# TFT_MicroSD.net
KiCad netlist of a schematic drawn in Altium Designer
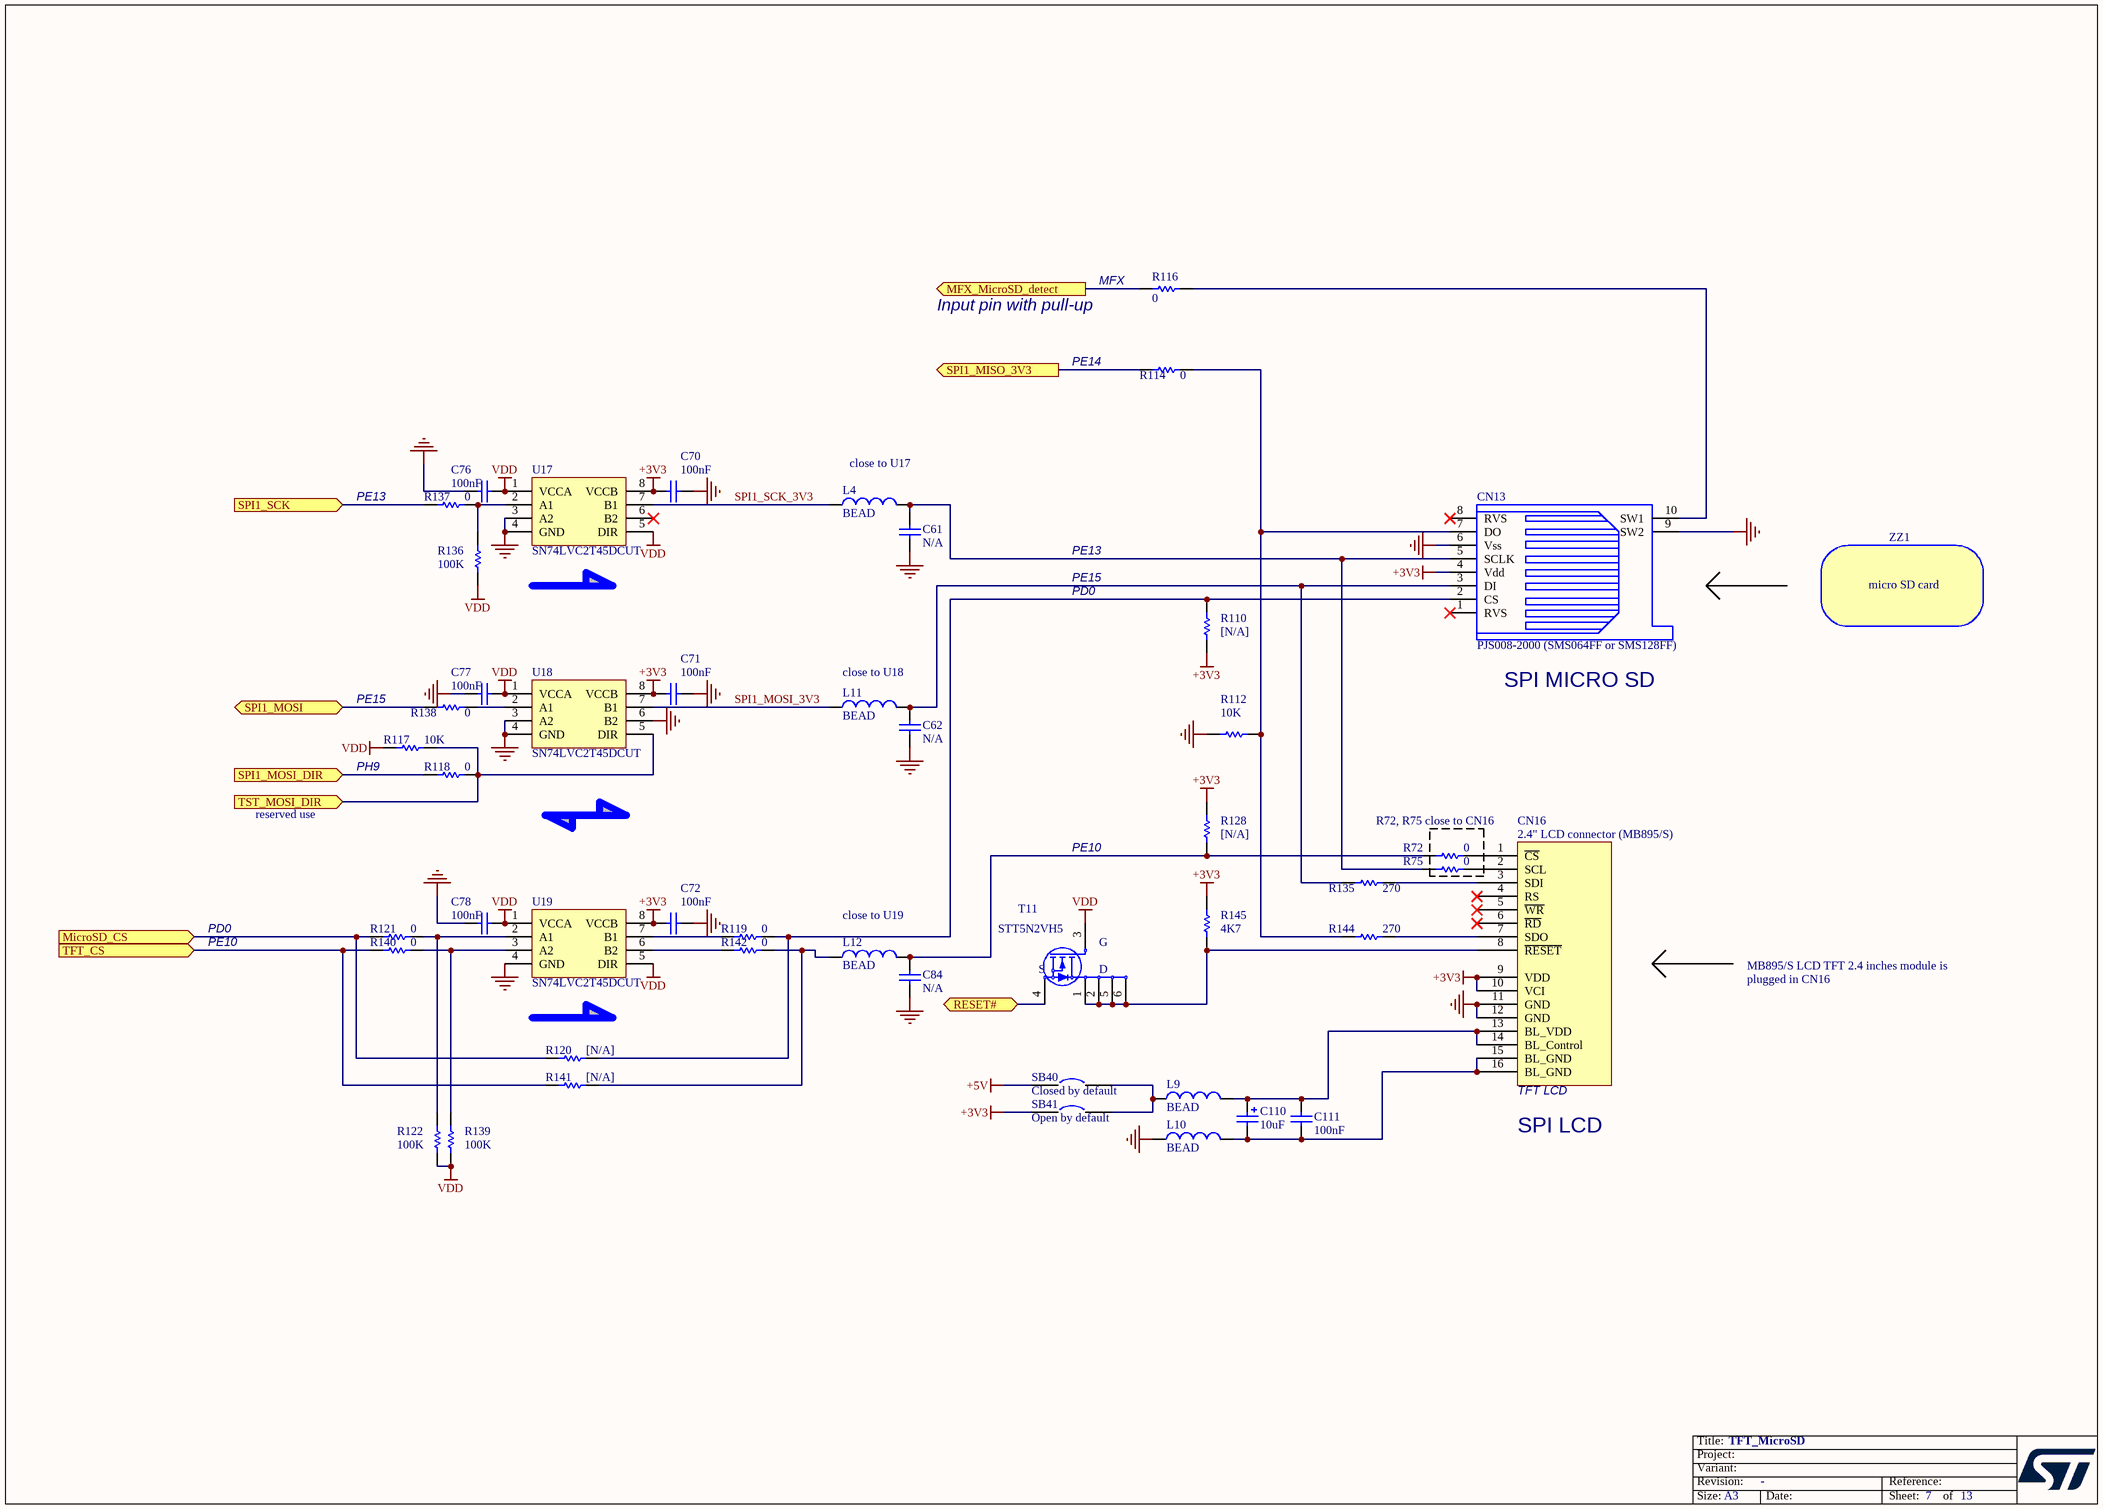
[diagram p0: TFT_MicroSD.SchDoc]

(export (version "E")
  (design (tool "Eeschema 10.0.6"))
  (components
    (comp (ref "C61")
      (value "N/A")
      (footprint "0603C")
      (description "Capacitor")
      (fields (field (name "PUBLISHER") "Altium Limited"))
      (libsource (lib "Miscellaneous Devices") (part "CAP"))
    )
    (comp (ref "C62")
      (value "N/A")
      (footprint "0603C")
      (description "Capacitor")
      (fields (field (name "PUBLISHER") "Altium Limited"))
      (libsource (lib "Miscellaneous Devices") (part "CAP"))
    )
    (comp (ref "C70")
      (value "100nF")
      (footprint "0402C")
      (description "Capacitor")
      (fields (field (name "PUBLISHER") "Altium Limited"))
      (libsource (lib "Miscellaneous Devices") (part "CAP"))
    )
    (comp (ref "C71")
      (value "100nF")
      (footprint "0402C")
      (description "Capacitor")
      (fields (field (name "PUBLISHER") "Altium Limited"))
      (libsource (lib "Miscellaneous Devices") (part "CAP"))
    )
    (comp (ref "C72")
      (value "100nF")
      (footprint "0402C")
      (description "Capacitor")
      (fields (field (name "PUBLISHER") "Altium Limited"))
      (libsource (lib "Miscellaneous Devices") (part "CAP"))
    )
    (comp (ref "C76")
      (value "100nF")
      (footprint "0402C")
      (description "Capacitor")
      (fields (field (name "PUBLISHER") "Altium Limited"))
      (libsource (lib "Miscellaneous Devices") (part "CAP"))
    )
    (comp (ref "C77")
      (value "100nF")
      (footprint "0402C")
      (description "Capacitor")
      (fields (field (name "PUBLISHER") "Altium Limited"))
      (libsource (lib "Miscellaneous Devices") (part "CAP"))
    )
    (comp (ref "C78")
      (value "100nF")
      (footprint "0402C")
      (description "Capacitor")
      (fields (field (name "PUBLISHER") "Altium Limited"))
      (libsource (lib "Miscellaneous Devices") (part "CAP"))
    )
    (comp (ref "C84")
      (value "N/A")
      (footprint "0603C")
      (description "Capacitor")
      (fields (field (name "PUBLISHER") "Altium Limited"))
      (libsource (lib "Miscellaneous Devices") (part "CAP"))
    )
    (comp (ref "C110")
      (value "10uF")
      (footprint "TAN-A")
      (description "Polarized Capacitor (Radial)")
      (fields (field (name "PUBLISHER") "Altium Limited"))
      (libsource (lib "Miscellaneous Devices") (part "Cap Pol1"))
    )
    (comp (ref "C111")
      (value "100nF")
      (footprint "0402C")
      (description "Capacitor")
      (fields (field (name "PUBLISHER") "Altium Limited"))
      (libsource (lib "Miscellaneous Devices") (part "Cap"))
    )
    (comp (ref "CN13")
      (value "PJS008-2000 (SMS064FF or SMS128FF)")
      (footprint "MSD_PJS008_")
      (libsource (lib "MB1070") (part "SMS016AFA5E"))
    )
    (comp (ref "CN16")
      (value "2.4\" LCD connector (MB895/S)")
      (footprint "MB895CS")
      (libsource (lib "MB1070") (part "ColorLCD_module"))
    )
    (comp (ref "L4")
      (value "BEAD")
      (footprint "0603L")
      (description "Bead,600R,350mA,0603")
      (fields (field (name "PUBLISHER") "Altium Limited"))
      (libsource (lib "Miscellaneous Devices") (part "Inductor"))
    )
    (comp (ref "L9")
      (value "BEAD")
      (footprint "0603L")
      (description "Bead,600R,350mA,0603")
      (fields (field (name "PUBLISHER") "Altium Limited"))
      (libsource (lib "Miscellaneous Devices") (part "Inductor"))
    )
    (comp (ref "L10")
      (value "BEAD")
      (footprint "0603L")
      (description "Bead,600R,350mA,0603")
      (fields (field (name "PUBLISHER") "Altium Limited"))
      (libsource (lib "Miscellaneous Devices") (part "Inductor"))
    )
    (comp (ref "L11")
      (value "BEAD")
      (footprint "0603L")
      (description "Bead,600R,350mA,0603")
      (fields (field (name "PUBLISHER") "Altium Limited"))
      (libsource (lib "Miscellaneous Devices") (part "Inductor"))
    )
    (comp (ref "L12")
      (value "BEAD")
      (footprint "0603L")
      (description "Bead,600R,350mA,0603")
      (fields (field (name "PUBLISHER") "Altium Limited"))
      (libsource (lib "Miscellaneous Devices") (part "Inductor"))
    )
    (comp (ref "R72")
      (value "0")
      (footprint "0603R")
      (description "Resistor")
      (fields (field (name "PUBLISHER") "Altium Limited"))
      (libsource (lib "Miscellaneous Devices") (part "Res1"))
    )
    (comp (ref "R75")
      (value "0")
      (footprint "0603R")
      (description "Resistor")
      (fields (field (name "PUBLISHER") "Altium Limited"))
      (libsource (lib "Miscellaneous Devices") (part "Res1"))
    )
    (comp (ref "R110")
      (value "[N/A]")
      (footprint "0603R")
      (description "Resistor")
      (fields (field (name "PUBLISHER") "Altium Limited"))
      (libsource (lib "Miscellaneous Devices") (part "Res1"))
    )
    (comp (ref "R112")
      (value "10K")
      (footprint "0402R")
      (description "Resistor")
      (fields (field (name "PUBLISHER") "Altium Limited"))
      (libsource (lib "Miscellaneous Devices") (part "Res1"))
    )
    (comp (ref "R114")
      (value "0")
      (footprint "0603R")
      (description "Resistor")
      (fields (field (name "PUBLISHER") "Altium Limited"))
      (libsource (lib "Miscellaneous Devices") (part "Res1"))
    )
    (comp (ref "R116")
      (value "0")
      (footprint "0603R")
      (description "Resistor")
      (fields (field (name "PUBLISHER") "Altium Limited"))
      (libsource (lib "Miscellaneous Devices") (part "Res1"))
    )
    (comp (ref "R117")
      (value "10K")
      (footprint "0402R")
      (description "Resistor")
      (fields (field (name "PUBLISHER") "Altium Limited"))
      (libsource (lib "Miscellaneous Devices") (part "Res1"))
    )
    (comp (ref "R118")
      (value "0")
      (footprint "0603R")
      (description "Resistor")
      (fields (field (name "PUBLISHER") "Altium Limited"))
      (libsource (lib "Miscellaneous Devices") (part "Res1"))
    )
    (comp (ref "R119")
      (value "0")
      (footprint "0603R")
      (description "Resistor")
      (fields (field (name "PUBLISHER") "Altium Limited"))
      (libsource (lib "Miscellaneous Devices") (part "res1"))
    )
    (comp (ref "R120")
      (value "[N/A]")
      (footprint "0603R")
      (description "Resistor")
      (fields (field (name "PUBLISHER") "Altium Limited"))
      (libsource (lib "Miscellaneous Devices") (part "Res1"))
    )
    (comp (ref "R121")
      (value "0")
      (footprint "0603R")
      (description "Resistor")
      (fields (field (name "PUBLISHER") "Altium Limited"))
      (libsource (lib "Miscellaneous Devices") (part "res1"))
    )
    (comp (ref "R122")
      (value "100K")
      (footprint "0603R")
      (description "Resistor")
      (fields (field (name "PUBLISHER") "Altium Limited"))
      (libsource (lib "Miscellaneous Devices") (part "Res1"))
    )
    (comp (ref "R128")
      (value "[N/A]")
      (footprint "0603R")
      (description "Resistor")
      (fields (field (name "PUBLISHER") "Altium Limited"))
      (libsource (lib "Miscellaneous Devices") (part "Res1"))
    )
    (comp (ref "R135")
      (value "270")
      (footprint "0603R")
      (description "Resistor")
      (fields (field (name "PUBLISHER") "Altium Limited"))
      (libsource (lib "Miscellaneous Devices") (part "Res1"))
    )
    (comp (ref "R136")
      (value "100K")
      (footprint "0603R")
      (description "Resistor")
      (fields (field (name "PUBLISHER") "Altium Limited"))
      (libsource (lib "Miscellaneous Devices") (part "Res1"))
    )
    (comp (ref "R137")
      (value "0")
      (footprint "0603R")
      (description "Resistor")
      (fields (field (name "PUBLISHER") "Altium Limited"))
      (libsource (lib "Miscellaneous Devices") (part "res1"))
    )
    (comp (ref "R138")
      (value "0")
      (footprint "0603R")
      (description "Resistor")
      (fields (field (name "PUBLISHER") "Altium Limited"))
      (libsource (lib "Miscellaneous Devices") (part "res1"))
    )
    (comp (ref "R139")
      (value "100K")
      (footprint "0603R")
      (description "Resistor")
      (fields (field (name "PUBLISHER") "Altium Limited"))
      (libsource (lib "Miscellaneous Devices") (part "Res1"))
    )
    (comp (ref "R140")
      (value "0")
      (footprint "0603R")
      (description "Resistor")
      (fields (field (name "PUBLISHER") "Altium Limited"))
      (libsource (lib "Miscellaneous Devices") (part "Res1"))
    )
    (comp (ref "R141")
      (value "[N/A]")
      (footprint "0603R")
      (description "Resistor")
      (fields (field (name "PUBLISHER") "Altium Limited"))
      (libsource (lib "Miscellaneous Devices") (part "Res1"))
    )
    (comp (ref "R142")
      (value "0")
      (footprint "0603R")
      (description "Resistor")
      (fields (field (name "PUBLISHER") "Altium Limited"))
      (libsource (lib "Miscellaneous Devices") (part "res1"))
    )
    (comp (ref "R144")
      (value "270")
      (footprint "0603R")
      (description "Resistor")
      (fields (field (name "PUBLISHER") "Altium Limited"))
      (libsource (lib "Miscellaneous Devices") (part "Res1"))
    )
    (comp (ref "R145")
      (value "4K7")
      (footprint "0402R")
      (description "Resistor")
      (fields (field (name "PUBLISHER") "Altium Limited"))
      (libsource (lib "Miscellaneous Devices") (part "Res1"))
    )
    (comp (ref "SB40")
      (value "Closed by default")
      (footprint "SB_0603")
      (description "Circuit Breaker")
      (fields (field (name "PUBLISHER") "Altium Limited"))
      (libsource (lib "Miscellaneous Devices") (part "Circuit Breaker"))
    )
    (comp (ref "SB41")
      (value "Open by default")
      (footprint "SB_0603")
      (description "Circuit Breaker")
      (fields (field (name "PUBLISHER") "Altium Limited"))
      (libsource (lib "Miscellaneous Devices") (part "Circuit Breaker"))
    )
    (comp (ref "T11")
      (value "STT5N2VH5")
      (footprint "SOT23-6L")
      (description "STripFETV Power MOSFET, N-CHANNEL 20V - 0.025 - 5A - SOT23-6L")
      (libsource (lib "MCD_TOOLS") (part "STT5N2VH5"))
    )
    (comp (ref "U17")
      (value "SN74LVC2T45DCUT")
      (footprint "USOP8_0R5_2X3R1")
      (libsource (lib "MB818") (part "SN74LVC2T45DCUT"))
    )
    (comp (ref "U18")
      (value "SN74LVC2T45DCUT")
      (footprint "USOP8_0R5_2X3R1")
      (libsource (lib "MB818") (part "SN74LVC2T45DCUT"))
    )
    (comp (ref "U19")
      (value "SN74LVC2T45DCUT")
      (footprint "USOP8_0R5_2X3R1")
      (libsource (lib "MB818") (part "SN74LVC2T45DCUT"))
    )
    (comp (ref "ZZ1")
      (value "micro SD card")
      (description "4GB or more")
      (libsource (lib "Almos") (part "BoM_Item"))
    )
  )
  (nets
    (net (code "1") (name "+3V3") (class "Default")
      (node (ref "C70") (pin "2") (pinfunction "2_2") (pintype "passive"))
      (node (ref "C71") (pin "2") (pinfunction "2_2") (pintype "passive"))
      (node (ref "C72") (pin "2") (pinfunction "2_2") (pintype "passive"))
      (node (ref "CN13") (pin "4") (pinfunction "Vdd_4") (pintype "passive"))
      (node (ref "CN16") (pin "10") (pinfunction "VCI_10") (pintype "passive"))
      (node (ref "CN16") (pin "9") (pinfunction "VDD_9") (pintype "passive"))
      (node (ref "R110") (pin "2") (pinfunction "2_2") (pintype "passive"))
      (node (ref "R128") (pin "2") (pinfunction "2_2") (pintype "passive"))
      (node (ref "R145") (pin "2") (pinfunction "2_2") (pintype "passive"))
      (node (ref "SB41") (pin "1") (pinfunction "1_1") (pintype "passive"))
      (node (ref "U17") (pin "8") (pinfunction "VCCB_8") (pintype "passive"))
      (node (ref "U18") (pin "8") (pinfunction "VCCB_8") (pintype "passive"))
      (node (ref "U19") (pin "8") (pinfunction "VCCB_8") (pintype "passive"))
    )
    (net (code "2") (name "+5V") (class "Default")
      (node (ref "SB40") (pin "1") (pinfunction "1_1") (pintype "passive"))
    )
    (net (code "3") (name "/MFX_MicroSD_detect") (class "Default")
      (node (ref "R116") (pin "1") (pinfunction "1_1") (pintype "passive"))
    )
    (net (code "4") (name "/MicroSD_CS") (class "Default")
      (node (ref "R120") (pin "1") (pinfunction "1_1") (pintype "passive"))
      (node (ref "R121") (pin "2") (pinfunction "2_2") (pintype "passive"))
    )
    (net (code "5") (name "/RESET#") (class "Default")
      (node (ref "T11") (pin "4") (pinfunction "S_4") (pintype "passive"))
    )
    (net (code "6") (name "/SPI1_MISO_3V3") (class "Default")
      (node (ref "R114") (pin "2") (pinfunction "2_2") (pintype "passive"))
    )
    (net (code "7") (name "/SPI1_MOSI") (class "Default")
      (node (ref "R138") (pin "2") (pinfunction "2_2") (pintype "passive"))
    )
    (net (code "8") (name "/SPI1_MOSI_3V3") (class "Default")
      (node (ref "L11") (pin "1") (pinfunction "1_1") (pintype "passive"))
      (node (ref "U18") (pin "7") (pinfunction "B1_7") (pintype "passive"))
    )
    (net (code "9") (name "/SPI1_MOSI_DIR") (class "Default")
      (node (ref "R118") (pin "2") (pinfunction "2_2") (pintype "passive"))
    )
    (net (code "10") (name "/SPI1_SCK") (class "Default")
      (node (ref "R137") (pin "2") (pinfunction "2_2") (pintype "passive"))
    )
    (net (code "11") (name "/SPI1_SCK_3V3") (class "Default")
      (node (ref "L4") (pin "1") (pinfunction "1_1") (pintype "passive"))
      (node (ref "U17") (pin "7") (pinfunction "B1_7") (pintype "passive"))
    )
    (net (code "12") (name "/TFT_CS") (class "Default")
      (node (ref "R140") (pin "1") (pinfunction "1_1") (pintype "passive"))
      (node (ref "R141") (pin "1") (pinfunction "1_1") (pintype "passive"))
    )
    (net (code "13") (name "/TST_MOSI_DIR") (class "Default")
      (node (ref "R117") (pin "1") (pinfunction "1_1") (pintype "passive"))
      (node (ref "R118") (pin "1") (pinfunction "1_1") (pintype "passive"))
      (node (ref "U18") (pin "5") (pinfunction "DIR_5") (pintype "passive"))
    )
    (net (code "14") (name "GND") (class "Default")
      (node (ref "C61") (pin "1") (pinfunction "1_1") (pintype "passive"))
      (node (ref "C62") (pin "1") (pinfunction "1_1") (pintype "passive"))
      (node (ref "C70") (pin "1") (pinfunction "1_1") (pintype "passive"))
      (node (ref "C71") (pin "1") (pinfunction "1_1") (pintype "passive"))
      (node (ref "C72") (pin "1") (pinfunction "1_1") (pintype "passive"))
      (node (ref "C76") (pin "1") (pinfunction "1_1") (pintype "passive"))
      (node (ref "C77") (pin "1") (pinfunction "1_1") (pintype "passive"))
      (node (ref "C78") (pin "1") (pinfunction "1_1") (pintype "passive"))
      (node (ref "C84") (pin "1") (pinfunction "1_1") (pintype "passive"))
      (node (ref "CN13") (pin "6") (pinfunction "Vss_6") (pintype "passive"))
      (node (ref "CN13") (pin "9") (pinfunction "SW2_9") (pintype "passive"))
      (node (ref "CN16") (pin "11") (pinfunction "GND_11") (pintype "passive"))
      (node (ref "CN16") (pin "12") (pinfunction "GND_12") (pintype "passive"))
      (node (ref "L10") (pin "1") (pinfunction "1_1") (pintype "passive"))
      (node (ref "R112") (pin "1") (pinfunction "1_1") (pintype "passive"))
      (node (ref "U17") (pin "3") (pinfunction "A2_3") (pintype "passive"))
      (node (ref "U17") (pin "4") (pinfunction "GND_4") (pintype "passive"))
      (node (ref "U18") (pin "3") (pinfunction "A2_3") (pintype "passive"))
      (node (ref "U18") (pin "4") (pinfunction "GND_4") (pintype "passive"))
      (node (ref "U18") (pin "6") (pinfunction "B2_6") (pintype "passive"))
      (node (ref "U19") (pin "4") (pinfunction "GND_4") (pintype "passive"))
    )
    (net (code "15") (name "Net-(C84-Pad2)") (class "Default")
      (node (ref "C84") (pin "2") (pinfunction "2_2") (pintype "passive"))
      (node (ref "L12") (pin "2") (pinfunction "2_2") (pintype "passive"))
      (node (ref "R128") (pin "1") (pinfunction "1_1") (pintype "passive"))
      (node (ref "R72") (pin "1") (pinfunction "1_1") (pintype "passive"))
    )
    (net (code "16") (name "Net-(C110-Pad2)") (class "Default")
      (node (ref "C110") (pin "2") (pinfunction "2_2") (pintype "passive"))
      (node (ref "C111") (pin "2") (pinfunction "2_2") (pintype "passive"))
      (node (ref "CN16") (pin "15") (pinfunction "BL_GND_15") (pintype "passive"))
      (node (ref "CN16") (pin "16") (pinfunction "BL_GND_16") (pintype "passive"))
      (node (ref "L10") (pin "2") (pinfunction "2_2") (pintype "passive"))
    )
    (net (code "17") (name "Net-(CN13-CS)") (class "Default")
      (node (ref "CN13") (pin "2") (pinfunction "CS_2") (pintype "passive"))
      (node (ref "R110") (pin "1") (pinfunction "1_1") (pintype "passive"))
      (node (ref "R119") (pin "1") (pinfunction "1_1") (pintype "passive"))
      (node (ref "R120") (pin "2") (pinfunction "2_2") (pintype "passive"))
    )
    (net (code "18") (name "Net-(CN13-DI)") (class "Default")
      (node (ref "C62") (pin "2") (pinfunction "2_2") (pintype "passive"))
      (node (ref "CN13") (pin "3") (pinfunction "DI_3") (pintype "passive"))
      (node (ref "L11") (pin "2") (pinfunction "2_2") (pintype "passive"))
      (node (ref "R135") (pin "2") (pinfunction "2_2") (pintype "passive"))
    )
    (net (code "19") (name "Net-(CN13-DO)") (class "Default")
      (node (ref "CN13") (pin "7") (pinfunction "DO_7") (pintype "passive"))
      (node (ref "R112") (pin "2") (pinfunction "2_2") (pintype "passive"))
      (node (ref "R114") (pin "1") (pinfunction "1_1") (pintype "passive"))
      (node (ref "R144") (pin "1") (pinfunction "1_1") (pintype "passive"))
    )
    (net (code "20") (name "Net-(CN13-SCLK)") (class "Default")
      (node (ref "C61") (pin "2") (pinfunction "2_2") (pintype "passive"))
      (node (ref "CN13") (pin "5") (pinfunction "SCLK_5") (pintype "passive"))
      (node (ref "L4") (pin "2") (pinfunction "2_2") (pintype "passive"))
      (node (ref "R75") (pin "1") (pinfunction "1_1") (pintype "passive"))
    )
    (net (code "21") (name "Net-(CN13-SW1)") (class "Default")
      (node (ref "CN13") (pin "10") (pinfunction "SW1_10") (pintype "passive"))
      (node (ref "R116") (pin "2") (pinfunction "2_2") (pintype "passive"))
    )
    (net (code "22") (name "Net-(CN16-BL_Control)") (class "Default")
      (node (ref "C110") (pin "1") (pinfunction "1_1") (pintype "passive"))
      (node (ref "C111") (pin "1") (pinfunction "1_1") (pintype "passive"))
      (node (ref "CN16") (pin "13") (pinfunction "BL_VDD_13") (pintype "passive"))
      (node (ref "CN16") (pin "14") (pinfunction "BL_Control_14") (pintype "passive"))
      (node (ref "L9") (pin "2") (pinfunction "2_2") (pintype "passive"))
    )
    (net (code "23") (name "Net-(CN16-SCL)") (class "Default")
      (node (ref "CN16") (pin "2") (pinfunction "SCL_2") (pintype "passive"))
      (node (ref "R75") (pin "2") (pinfunction "2_2") (pintype "passive"))
    )
    (net (code "24") (name "Net-(CN16-SDI)") (class "Default")
      (node (ref "CN16") (pin "3") (pinfunction "SDI_3") (pintype "passive"))
      (node (ref "R135") (pin "1") (pinfunction "1_1") (pintype "passive"))
    )
    (net (code "25") (name "Net-(CN16-SDO)") (class "Default")
      (node (ref "CN16") (pin "7") (pinfunction "SDO_7") (pintype "passive"))
      (node (ref "R144") (pin "2") (pinfunction "2_2") (pintype "passive"))
    )
    (net (code "26") (name "Net-(CN16-~{CS})") (class "Default")
      (node (ref "CN16") (pin "1") (pinfunction "~{CS}_1") (pintype "passive"))
      (node (ref "R72") (pin "2") (pinfunction "2_2") (pintype "passive"))
    )
    (net (code "27") (name "Net-(CN16-~{RESET})") (class "Default")
      (node (ref "CN16") (pin "8") (pinfunction "~{RESET}_8") (pintype "passive"))
      (node (ref "R145") (pin "1") (pinfunction "1_1") (pintype "passive"))
      (node (ref "T11") (pin "1") (pinfunction "S_1") (pintype "passive"))
      (node (ref "T11") (pin "2") (pinfunction "S_2") (pintype "passive"))
      (node (ref "T11") (pin "5") (pinfunction "D_5") (pintype "passive"))
      (node (ref "T11") (pin "6") (pinfunction "D_6") (pintype "passive"))
    )
    (net (code "28") (name "Net-(L9-Pad1)") (class "Default")
      (node (ref "L9") (pin "1") (pinfunction "1_1") (pintype "passive"))
      (node (ref "SB40") (pin "2") (pinfunction "2_2") (pintype "passive"))
      (node (ref "SB41") (pin "2") (pinfunction "2_2") (pintype "passive"))
    )
    (net (code "29") (name "Net-(L12-Pad1)") (class "Default")
      (node (ref "L12") (pin "1") (pinfunction "1_1") (pintype "passive"))
      (node (ref "R141") (pin "2") (pinfunction "2_2") (pintype "passive"))
      (node (ref "R142") (pin "1") (pinfunction "1_1") (pintype "passive"))
    )
    (net (code "30") (name "Net-(U17-A1)") (class "Default")
      (node (ref "R136") (pin "1") (pinfunction "1_1") (pintype "passive"))
      (node (ref "R137") (pin "1") (pinfunction "1_1") (pintype "passive"))
      (node (ref "U17") (pin "2") (pinfunction "A1_2") (pintype "passive"))
    )
    (net (code "31") (name "Net-(U18-A1)") (class "Default")
      (node (ref "R138") (pin "1") (pinfunction "1_1") (pintype "passive"))
      (node (ref "U18") (pin "2") (pinfunction "A1_2") (pintype "passive"))
    )
    (net (code "32") (name "Net-(U19-A1)") (class "Default")
      (node (ref "R121") (pin "1") (pinfunction "1_1") (pintype "passive"))
      (node (ref "R122") (pin "1") (pinfunction "1_1") (pintype "passive"))
      (node (ref "U19") (pin "2") (pinfunction "A1_2") (pintype "passive"))
    )
    (net (code "33") (name "Net-(U19-A2)") (class "Default")
      (node (ref "R139") (pin "1") (pinfunction "1_1") (pintype "passive"))
      (node (ref "R140") (pin "2") (pinfunction "2_2") (pintype "passive"))
      (node (ref "U19") (pin "3") (pinfunction "A2_3") (pintype "passive"))
    )
    (net (code "34") (name "Net-(U19-B1)") (class "Default")
      (node (ref "R119") (pin "2") (pinfunction "2_2") (pintype "passive"))
      (node (ref "U19") (pin "7") (pinfunction "B1_7") (pintype "passive"))
    )
    (net (code "35") (name "Net-(U19-B2)") (class "Default")
      (node (ref "R142") (pin "2") (pinfunction "2_2") (pintype "passive"))
      (node (ref "U19") (pin "6") (pinfunction "B2_6") (pintype "passive"))
    )
    (net (code "36") (name "VDD") (class "Default")
      (node (ref "C76") (pin "2") (pinfunction "2_2") (pintype "passive"))
      (node (ref "C77") (pin "2") (pinfunction "2_2") (pintype "passive"))
      (node (ref "C78") (pin "2") (pinfunction "2_2") (pintype "passive"))
      (node (ref "R117") (pin "2") (pinfunction "2_2") (pintype "passive"))
      (node (ref "R122") (pin "2") (pinfunction "2_2") (pintype "passive"))
      (node (ref "R136") (pin "2") (pinfunction "2_2") (pintype "passive"))
      (node (ref "R139") (pin "2") (pinfunction "2_2") (pintype "passive"))
      (node (ref "T11") (pin "3") (pinfunction "G_3") (pintype "passive"))
      (node (ref "U17") (pin "1") (pinfunction "VCCA_1") (pintype "passive"))
      (node (ref "U17") (pin "5") (pinfunction "DIR_5") (pintype "passive"))
      (node (ref "U18") (pin "1") (pinfunction "VCCA_1") (pintype "passive"))
      (node (ref "U19") (pin "1") (pinfunction "VCCA_1") (pintype "passive"))
      (node (ref "U19") (pin "5") (pinfunction "DIR_5") (pintype "passive"))
    )
    (net (code "37") (name "unconnected-(CN13-RVS-Pad1)") (class "Default")
      (node (ref "CN13") (pin "1") (pinfunction "RVS_1") (pintype "passive+no_connect"))
    )
    (net (code "38") (name "unconnected-(CN13-RVS-Pad8)") (class "Default")
      (node (ref "CN13") (pin "8") (pinfunction "RVS_8") (pintype "passive+no_connect"))
    )
    (net (code "39") (name "unconnected-(CN16-RS-Pad4)") (class "Default")
      (node (ref "CN16") (pin "4") (pinfunction "RS_4") (pintype "passive+no_connect"))
    )
    (net (code "40") (name "unconnected-(CN16-~{RD}-Pad6)") (class "Default")
      (node (ref "CN16") (pin "6") (pinfunction "~{RD}_6") (pintype "passive+no_connect"))
    )
    (net (code "41") (name "unconnected-(CN16-~{WR}-Pad5)") (class "Default")
      (node (ref "CN16") (pin "5") (pinfunction "~{WR}_5") (pintype "passive+no_connect"))
    )
    (net (code "42") (name "unconnected-(U17-B2-Pad6)") (class "Default")
      (node (ref "U17") (pin "6") (pinfunction "B2_6") (pintype "passive+no_connect"))
    )
  )
)
